# 11_USB.net
KiCad netlist of a schematic drawn in Altium Designer
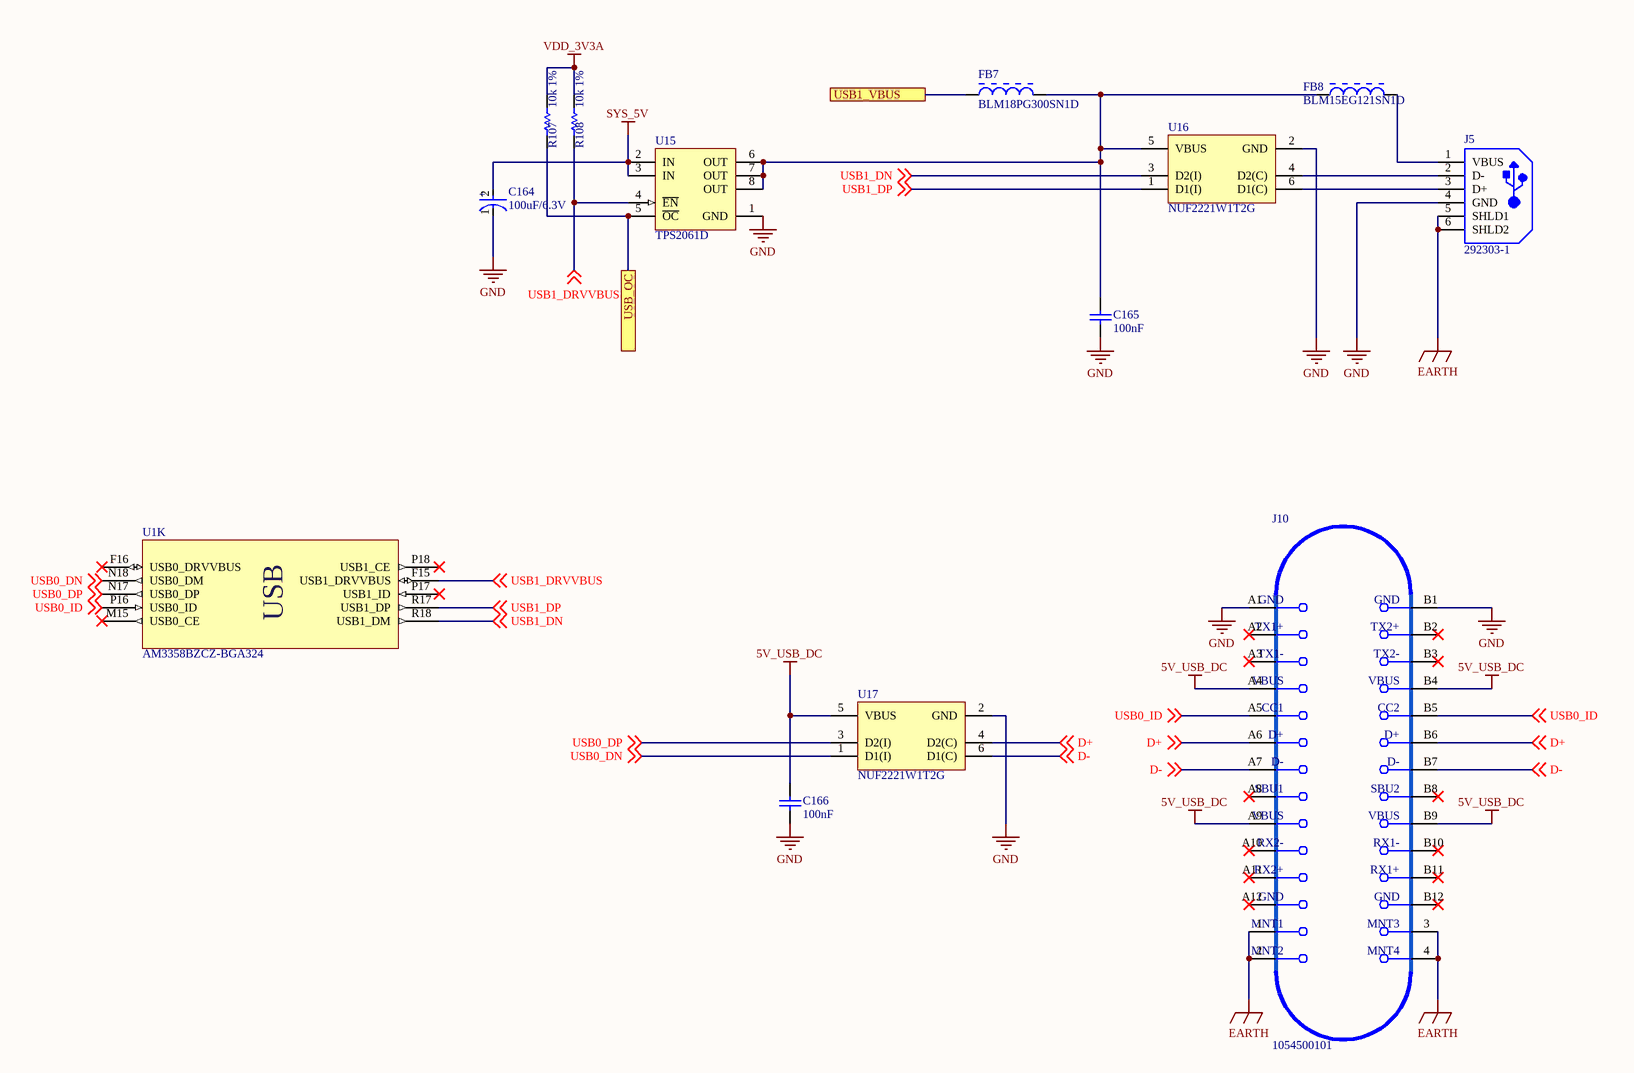
[diagram p0: 11. USB.SchDoc]

(export (version "E")
  (design (tool "Eeschema 10.0.6"))
  (components
    (comp (ref "C164")
      (value "100uF/6.3V")
      (footprint "FP-NLJB-MFG")
      (description "CAP NIOB OXI 100UF 20% 6.3V 1210")
      (fields
        (field (name "MANUFACTURER") "AVX Corporation")
        (field (name "MANUFACTURER PART NUMBER") "NLJB107M006R1700")
      )
      (libsource (lib "Altium Content Vault") (part "a00bbbee19879c290e62620ae7e47b1"))
    )
    (comp (ref "C165")
      (value "100nF")
      (footprint "CAPC1005X55X25LL05T10")
      (description "Chip Capacitor, 0.1 uF, +/- 10%, 16 V, -55 to 125 degC, 0402 (1005 Metric), RoHS, Tape and Reel")
      (fields (field (name "VOLTAGE") "16V") (field (name "TOLERANCE") "10%"))
      (libsource (lib "Altium Content Vault") (part "CAP-NP-2"))
    )
    (comp (ref "C166")
      (value "100nF")
      (footprint "CAPC1005X55X25LL05T10")
      (description "Chip Capacitor, 0.1 uF, +/- 10%, 16 V, -55 to 125 degC, 0402 (1005 Metric), RoHS, Tape and Reel")
      (fields (field (name "VOLTAGE") "16V") (field (name "TOLERANCE") "10%"))
      (libsource (lib "Altium Content Vault") (part "CAP-NP-2"))
    )
    (comp (ref "FB7")
      (value "BLM18PG300SN1D")
      (footprint "MURA-BLM18PG_KG-CHIP-2_V1")
      (fields (field (name "MANUFACTURER") "Murata"))
      (libsource (lib "Altium Content Vault") (part "MURA-FB-2"))
    )
    (comp (ref "FB8")
      (value "BLM15EG121SN1D")
      (footprint "MURA-BLM15-CHIP-2_V")
      (fields (field (name "MANUFACTURER") "Murata"))
      (libsource (lib "Altium Content Vault") (part "MURA-FB-2"))
    )
    (comp (ref "J5")
      (value "292303-1")
      (footprint "TE-292303-1_V")
      (fields (field (name "MANUFACTURER") "TE Connectivity"))
      (libsource (lib "Altium Content Vault") (part "USB-4-2SHLD"))
    )
    (comp (ref "J10")
      (value "1054500101")
      (footprint "FP-1054500101-MFG")
      (description "CONN RCP USB3.1 TYPEC 24P SMD RA")
      (fields
        (field (name "MANUFACTURER") "Molex")
        (field (name "OCTOPART") "https://octopart.com/105450-0101-molex-68082325")
      )
      (libsource (lib "SyTungNguyen") (part "USB-C"))
    )
    (comp (ref "R107")
      (value "10k 1%")
      (footprint "RESC1005X40X25LL05T05")
      (description "10k 0.063W 1% 0402 (1005 Metric)  SMD")
      (fields (field (name "MANUFACTURER") "Vishay Dale") (field (name "PART NUMBER") "CRCW040210K0FKED"))
      (libsource (lib "AM3358_DEV_BOARD") (part "RES"))
    )
    (comp (ref "R108")
      (value "10k 1%")
      (footprint "RESC1005X40X25LL05T05")
      (description "10k 0.063W 1% 0402 (1005 Metric)  SMD")
      (fields (field (name "MANUFACTURER") "Vishay Dale") (field (name "PART NUMBER") "CRCW040210K0FKED"))
      (libsource (lib "AM3358_DEV_BOARD") (part "RES"))
    )
    (comp (ref "U1")
      (value "AM3358BZCZ-BGA324")
      (footprint "TI-ZCZ324")
      (libsource (lib "SyTungNguyen") (part "AM3358BZCZ100"))
    )
    (comp (ref "U15")
      (value "TPS2061D")
      (footprint "D0008A_N")
      (fields (field (name "MANUFACTURER") "Texas Instruments"))
      (libsource (lib "Altium Content Vault") (part "TI-TPS2061D8"))
    )
    (comp (ref "U16")
      (value "NUF2221W1T2G")
      (footprint "ONSC-SC70-6-419B-02_W_V")
      (description "USB Upstream Terminator with ESD Protection, -55 to 125 degC, 6-Pin SC70, Pb-Free, Tape and Reel")
      (fields (field (name "MANUFACTURER") "On Semiconductor"))
      (libsource (lib "Altium Content Vault") (part "ONSC-NUF2221-SC-88-6-419B-02"))
    )
    (comp (ref "U17")
      (value "NUF2221W1T2G")
      (footprint "ONSC-SC70-6-419B-02_W_V")
      (description "USB Upstream Terminator with ESD Protection, -55 to 125 degC, 6-Pin SC70, Pb-Free, Tape and Reel")
      (fields (field (name "MANUFACTURER") "On Semiconductor"))
      (libsource (lib "Altium Content Vault") (part "ONSC-NUF2221-SC-88-6-419B-02"))
    )
  )
  (nets
    (net (code "1") (name "/USB1_VBUS") (class "Default")
      (node (ref "FB7") (pin "1") (pinfunction "1_1") (pintype "passive"))
    )
    (net (code "2") (name "/USB_OC") (class "Default")
      (node (ref "R107") (pin "1") (pinfunction "1_1") (pintype "passive"))
      (node (ref "U15") (pin "5") (pinfunction "~{OC}_5") (pintype "open_collector"))
    )
    (net (code "3") (name "5V_USB_DC") (class "Default")
      (node (ref "C166") (pin "2") (pinfunction "2_2") (pintype "passive"))
      (node (ref "J10") (pin "A4") (pinfunction "VBUS_A4") (pintype "passive"))
      (node (ref "J10") (pin "A9") (pinfunction "VBUS_A9") (pintype "passive"))
      (node (ref "J10") (pin "B4") (pinfunction "VBUS_B4") (pintype "passive"))
      (node (ref "J10") (pin "B9") (pinfunction "VBUS_B9") (pintype "passive"))
      (node (ref "U17") (pin "5") (pinfunction "VBUS_5") (pintype "power_in"))
    )
    (net (code "4") (name "D+") (class "Default")
      (node (ref "J10") (pin "A6") (pinfunction "D+_A6") (pintype "passive"))
      (node (ref "J10") (pin "B6") (pinfunction "D+_B6") (pintype "passive"))
      (node (ref "U17") (pin "4") (pinfunction "D2(C)_4") (pintype "passive"))
    )
    (net (code "5") (name "D-") (class "Default")
      (node (ref "J10") (pin "A7") (pinfunction "D-_A7") (pintype "passive"))
      (node (ref "J10") (pin "B7") (pinfunction "D-_B7") (pintype "passive"))
      (node (ref "U17") (pin "6") (pinfunction "D1(C)_6") (pintype "passive"))
    )
    (net (code "6") (name "EARTH") (class "Default")
      (node (ref "J10") (pin "1") (pinfunction "MNT_1_1") (pintype "passive"))
      (node (ref "J10") (pin "2") (pinfunction "MNT_2_2") (pintype "passive"))
      (node (ref "J10") (pin "3") (pinfunction "MNT_3_3") (pintype "passive"))
      (node (ref "J10") (pin "4") (pinfunction "MNT_4_4") (pintype "passive"))
      (node (ref "J5") (pin "5") (pinfunction "SHLD1_5") (pintype "passive"))
      (node (ref "J5") (pin "6") (pinfunction "SHLD2_6") (pintype "passive"))
    )
    (net (code "7") (name "GND") (class "Default")
      (node (ref "C164") (pin "1") (pinfunction "C_1") (pintype "passive"))
      (node (ref "C165") (pin "1") (pinfunction "1_1") (pintype "passive"))
      (node (ref "C166") (pin "1") (pinfunction "1_1") (pintype "passive"))
      (node (ref "J10") (pin "A1") (pinfunction "GND_A1") (pintype "passive"))
      (node (ref "J10") (pin "B1") (pinfunction "GND_B1") (pintype "passive"))
      (node (ref "J5") (pin "4") (pinfunction "GND_4") (pintype "passive"))
      (node (ref "U15") (pin "1") (pinfunction "GND_1") (pintype "power_in"))
      (node (ref "U16") (pin "2") (pinfunction "GND_2") (pintype "power_in"))
      (node (ref "U17") (pin "2") (pinfunction "GND_2") (pintype "power_in"))
    )
    (net (code "8") (name "Net-(J5-D+)") (class "Default")
      (node (ref "J5") (pin "3") (pinfunction "D+_3") (pintype "passive"))
      (node (ref "U16") (pin "6") (pinfunction "D1(C)_6") (pintype "passive"))
    )
    (net (code "9") (name "Net-(J5-D-)") (class "Default")
      (node (ref "J5") (pin "2") (pinfunction "D-_2") (pintype "passive"))
      (node (ref "U16") (pin "4") (pinfunction "D2(C)_4") (pintype "passive"))
    )
    (net (code "10") (name "Net-(J5-VBUS)") (class "Default")
      (node (ref "FB8") (pin "2") (pinfunction "2_2") (pintype "passive"))
      (node (ref "J5") (pin "1") (pinfunction "VBUS_1") (pintype "passive"))
    )
    (net (code "11") (name "Net-(U16-VBUS)") (class "Default")
      (node (ref "C165") (pin "2") (pinfunction "2_2") (pintype "passive"))
      (node (ref "FB7") (pin "2") (pinfunction "2_2") (pintype "passive"))
      (node (ref "FB8") (pin "1") (pinfunction "1_1") (pintype "passive"))
      (node (ref "U15") (pin "6") (pinfunction "OUT_6") (pintype "power_in"))
      (node (ref "U15") (pin "7") (pinfunction "OUT_7") (pintype "power_in"))
      (node (ref "U15") (pin "8") (pinfunction "OUT_8") (pintype "power_in"))
      (node (ref "U16") (pin "5") (pinfunction "VBUS_5") (pintype "power_in"))
    )
    (net (code "12") (name "SYS_5V") (class "Default")
      (node (ref "C164") (pin "2") (pinfunction "A_2") (pintype "passive"))
      (node (ref "U15") (pin "2") (pinfunction "IN_2") (pintype "power_in"))
      (node (ref "U15") (pin "3") (pinfunction "IN_3") (pintype "power_in"))
    )
    (net (code "13") (name "USB0_DN") (class "Default")
      (node (ref "U1") (pin "N18") (pinfunction "USB0_DM_N18") (pintype "output"))
      (node (ref "U17") (pin "1") (pinfunction "D1(I)_1") (pintype "passive"))
    )
    (net (code "14") (name "USB0_DP") (class "Default")
      (node (ref "U1") (pin "N17") (pinfunction "USB0_DP_N17") (pintype "output"))
      (node (ref "U17") (pin "3") (pinfunction "D2(I)_3") (pintype "passive"))
    )
    (net (code "15") (name "USB0_ID") (class "Default")
      (node (ref "J10") (pin "A5") (pinfunction "CC1_A5") (pintype "passive"))
      (node (ref "J10") (pin "B5") (pinfunction "CC2_B5") (pintype "passive"))
      (node (ref "U1") (pin "P16") (pinfunction "USB0_ID_P16") (pintype "input"))
    )
    (net (code "16") (name "USB1_DN") (class "Default")
      (node (ref "U1") (pin "R18") (pinfunction "USB1_DM_R18") (pintype "output"))
      (node (ref "U16") (pin "3") (pinfunction "D2(I)_3") (pintype "passive"))
    )
    (net (code "17") (name "USB1_DP") (class "Default")
      (node (ref "U1") (pin "R17") (pinfunction "USB1_DP_R17") (pintype "output"))
      (node (ref "U16") (pin "1") (pinfunction "D1(I)_1") (pintype "passive"))
    )
    (net (code "18") (name "USB1_DRVVBUS") (class "Default")
      (node (ref "R108") (pin "1") (pinfunction "1_1") (pintype "passive"))
      (node (ref "U1") (pin "F15") (pinfunction "USB1_DRVVBUS_F15") (pintype "bidirectional"))
      (node (ref "U15") (pin "4") (pinfunction "~{EN}_4") (pintype "input"))
    )
    (net (code "19") (name "VDD_3V3A") (class "Default")
      (node (ref "R107") (pin "2") (pinfunction "2_2") (pintype "passive"))
      (node (ref "R108") (pin "2") (pinfunction "2_2") (pintype "passive"))
    )
    (net (code "20") (name "unconnected-(J10-GND-PadA12)") (class "Default")
      (node (ref "J10") (pin "A12") (pinfunction "GND_A12") (pintype "passive+no_connect"))
    )
    (net (code "21") (name "unconnected-(J10-GND-PadB12)") (class "Default")
      (node (ref "J10") (pin "B12") (pinfunction "GND_B12") (pintype "passive+no_connect"))
    )
    (net (code "22") (name "unconnected-(J10-RX1+-PadB11)") (class "Default")
      (node (ref "J10") (pin "B11") (pinfunction "RX1+_B11") (pintype "passive+no_connect"))
    )
    (net (code "23") (name "unconnected-(J10-RX1--PadB10)") (class "Default")
      (node (ref "J10") (pin "B10") (pinfunction "RX1-_B10") (pintype "passive+no_connect"))
    )
    (net (code "24") (name "unconnected-(J10-RX2+-PadA11)") (class "Default")
      (node (ref "J10") (pin "A11") (pinfunction "RX2+_A11") (pintype "passive+no_connect"))
    )
    (net (code "25") (name "unconnected-(J10-RX2--PadA10)") (class "Default")
      (node (ref "J10") (pin "A10") (pinfunction "RX2-_A10") (pintype "passive+no_connect"))
    )
    (net (code "26") (name "unconnected-(J10-SBU1-PadA8)") (class "Default")
      (node (ref "J10") (pin "A8") (pinfunction "SBU1_A8") (pintype "passive+no_connect"))
    )
    (net (code "27") (name "unconnected-(J10-SBU2-PadB8)") (class "Default")
      (node (ref "J10") (pin "B8") (pinfunction "SBU2_B8") (pintype "passive+no_connect"))
    )
    (net (code "28") (name "unconnected-(J10-TX1+-PadA2)") (class "Default")
      (node (ref "J10") (pin "A2") (pinfunction "TX1+_A2") (pintype "passive+no_connect"))
    )
    (net (code "29") (name "unconnected-(J10-TX1--PadA3)") (class "Default")
      (node (ref "J10") (pin "A3") (pinfunction "TX1-_A3") (pintype "passive+no_connect"))
    )
    (net (code "30") (name "unconnected-(J10-TX2+-PadB2)") (class "Default")
      (node (ref "J10") (pin "B2") (pinfunction "TX2+_B2") (pintype "passive+no_connect"))
    )
    (net (code "31") (name "unconnected-(J10-TX2--PadB3)") (class "Default")
      (node (ref "J10") (pin "B3") (pinfunction "TX2-_B3") (pintype "passive+no_connect"))
    )
    (net (code "32") (name "unconnected-(U1K-USB0_CE-PadM15)") (class "Default")
      (node (ref "U1") (pin "M15") (pinfunction "USB0_CE_M15") (pintype "output+no_connect"))
    )
    (net (code "33") (name "unconnected-(U1K-USB0_DRVVBUS-PadF16)") (class "Default")
      (node (ref "U1") (pin "F16") (pinfunction "USB0_DRVVBUS_F16") (pintype "bidirectional+no_connect"))
    )
    (net (code "34") (name "unconnected-(U1K-USB1_CE-PadP18)") (class "Default")
      (node (ref "U1") (pin "P18") (pinfunction "USB1_CE_P18") (pintype "output+no_connect"))
    )
    (net (code "35") (name "unconnected-(U1K-USB1_ID-PadP17)") (class "Default")
      (node (ref "U1") (pin "P17") (pinfunction "USB1_ID_P17") (pintype "input+no_connect"))
    )
  )
)
